# BG96.net
KiCad netlist of a schematic drawn in Altium Designer
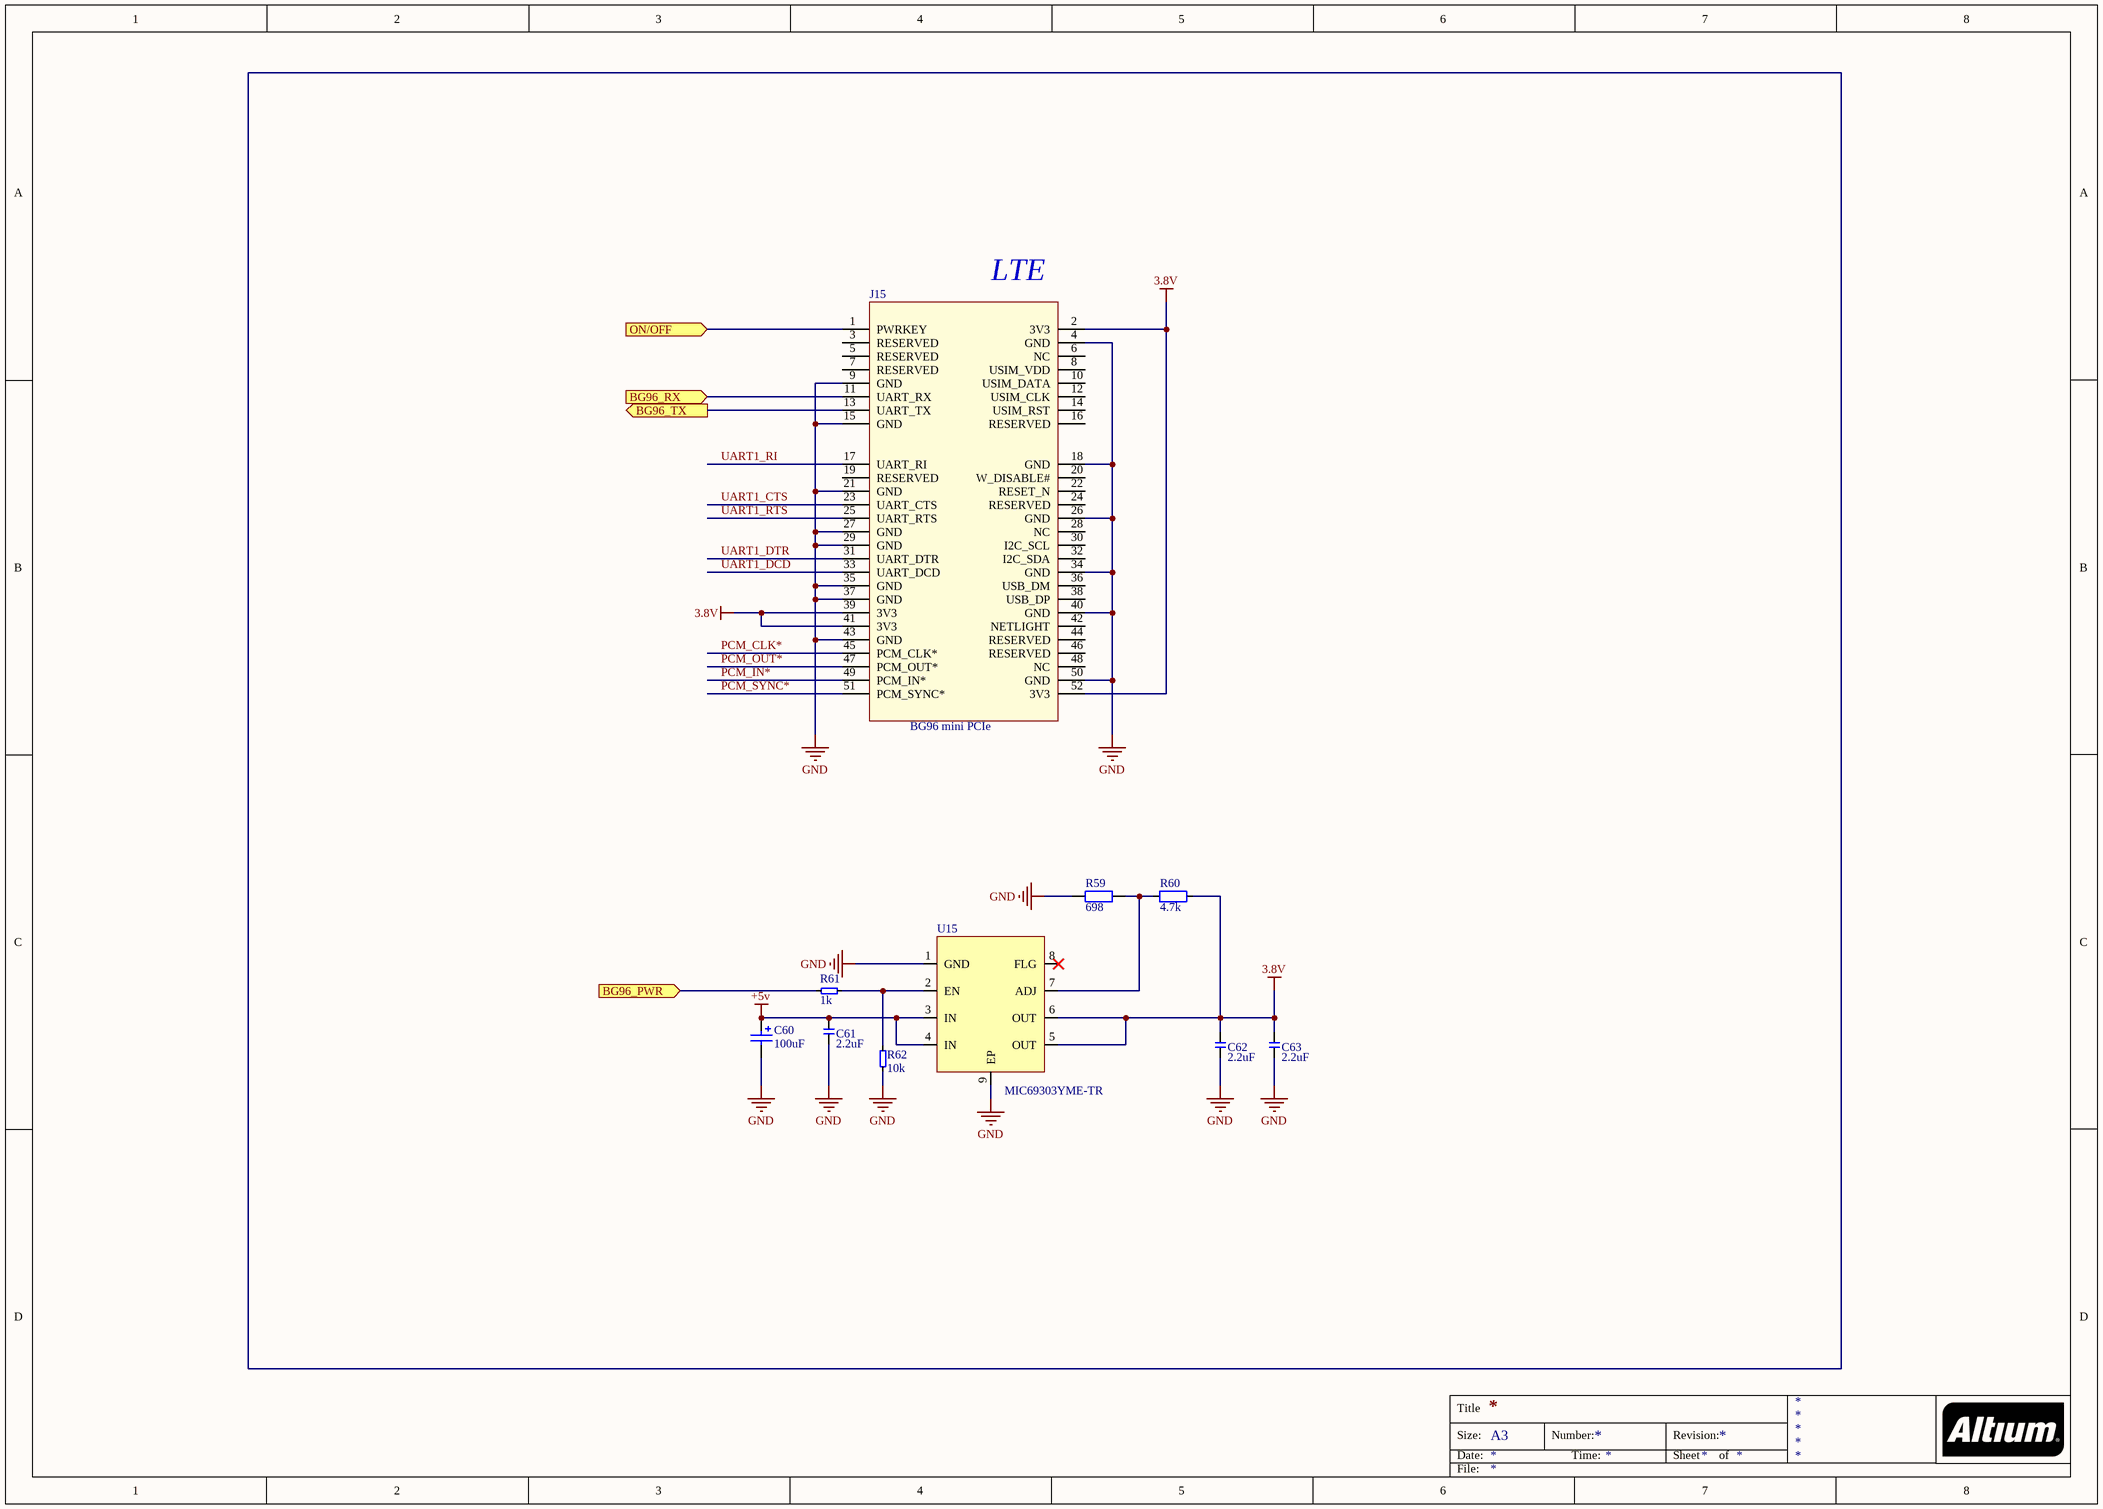
[diagram p0: BG96.SchDoc]

(export (version "E")
  (design (tool "Eeschema 10.0.6"))
  (components
    (comp (ref "C60")
      (value "100uF")
      (footprint "C_Tantalum_1206_(3.20mm x 1.60mm)")
      (description "CAP TANT 100UF 10% 6.3V 1206")
      (fields
        (field (name "MANUFACTURER") "Kyocera AVX")
        (field (name "MANUFACTURER PART NUMBER") "F930J107KAA")
      )
      (libsource (lib "Miscellaneous Devices") (part "Cap Pol2"))
    )
    (comp (ref "C61")
      (value "2.2uF")
      (footprint "C0603")
      (description "CAP CER 2.2UF 10V X7R 0603")
      (fields
        (field (name "MANUFACTURER") "Samsung")
        (field (name "MANUFACTURER PART NUMBER") "CL10B225KP8NNNC")
      )
      (libsource (lib "LED_LIB") (part "CAP_0603"))
    )
    (comp (ref "C62")
      (value "2.2uF")
      (footprint "C0603")
      (description "CAP CER 2.2UF 10V X7R 0603")
      (fields
        (field (name "MANUFACTURER") "Samsung")
        (field (name "MANUFACTURER PART NUMBER") "CL10B225KP8NNNC")
      )
      (libsource (lib "LED_LIB") (part "CAP_0603"))
    )
    (comp (ref "C63")
      (value "2.2uF")
      (footprint "C0603")
      (description "CAP CER 2.2UF 10V X7R 0603")
      (fields
        (field (name "MANUFACTURER") "Samsung")
        (field (name "MANUFACTURER PART NUMBER") "CL10B225KP8NNNC")
      )
      (libsource (lib "LED_LIB") (part "CAP_0603"))
    )
    (comp (ref "J15")
      (value "BG96 mini PCIe")
      (footprint "MiniPCIe_67910-5700")
      (description "LTE duaghter board")
      (fields
        (field (name "MANUFACTURER") "Texas Instruments")
        (field (name "MANUFACTURER PART NUMBER") "TPS54561DPRR")
      )
      (libsource (lib "4ADI_2DO") (part "BG96 mini PCIe"))
    )
    (comp (ref "R59")
      (value "698")
      (footprint "R0603")
      (description "RES SMD 698 OHM 1% 1/10W 0603")
      (fields
        (field (name "MANUFACTURER") "Yageo")
        (field (name "MANUFACTURER PART NUMBER") "RC0603FR-07698RL")
      )
      (libsource (lib "Miscellaneous Devices") (part "Res2"))
    )
    (comp (ref "R60")
      (value "4.7k")
      (footprint "R0603")
      (description "RES SMD 4.7K OHM 1% 1/10W 0603")
      (fields
        (field (name "MANUFACTURER") "Yageo Phycomp")
        (field (name "MANUFACTURER PART NUMBER") "RC0603FR-074K7L")
      )
      (libsource (lib "MY SCH LIB") (part "Res_0603"))
    )
    (comp (ref "R61")
      (value "1k")
      (footprint "R_0603")
      (description "RES SMD 1K OHM 1% 1/10W 0603")
      (fields
        (field (name "MANUFACTURER") "Yageo")
        (field (name "MANUFACTURER PART NUMBER") "RC0603FR-071KL")
      )
      (libsource (lib "LED_LIB") (part "R_0402"))
    )
    (comp (ref "R62")
      (value "10k")
      (footprint "R_0603")
      (description "RES SMD 10K OHM 1% 1/10W 0603")
      (fields
        (field (name "MANUFACTURER") "Yageo")
        (field (name "MANUFACTURER PART NUMBER") "RC0603FR-0710KL")
      )
      (libsource (lib "LED_LIB") (part "R_0402"))
    )
    (comp (ref "U15")
      (value "MIC69303YME-TR")
      (footprint "soic8 PowerPad")
      (description "IC REG LINEAR POS ADJ 3A 8SOIC")
      (fields (field (name "MANUFACTURER") "Microchip Technology"))
      (libsource (lib "4ADI_2DO") (part "MIC69303YME-TR"))
    )
  )
  (nets
    (net (code "1") (name "+5v") (class "Default")
      (node (ref "C60") (pin "1") (pinfunction "1_1") (pintype "passive"))
      (node (ref "C61") (pin "2") (pinfunction "2_2") (pintype "passive"))
      (node (ref "U15") (pin "3") (pinfunction "IN_3") (pintype "passive"))
      (node (ref "U15") (pin "4") (pinfunction "IN_4") (pintype "passive"))
    )
    (net (code "2") (name "/BG96_PWR") (class "Default")
      (node (ref "R61") (pin "1") (pinfunction "1_1") (pintype "passive"))
    )
    (net (code "3") (name "/BG96_RX") (class "Default")
      (node (ref "J15") (pin "11") (pinfunction "UART_RX_11") (pintype "passive"))
    )
    (net (code "4") (name "/BG96_TX") (class "Default")
      (node (ref "J15") (pin "13") (pinfunction "UART_TX_13") (pintype "passive"))
    )
    (net (code "5") (name "/ON{slash}OFF") (class "Default")
      (node (ref "J15") (pin "1") (pinfunction "PWRKEY_1") (pintype "passive"))
    )
    (net (code "6") (name "/PCM_CLK*") (class "Default")
      (node (ref "J15") (pin "45") (pinfunction "PCM_CLK*_45") (pintype "passive"))
    )
    (net (code "7") (name "/PCM_IN*") (class "Default")
      (node (ref "J15") (pin "49") (pinfunction "PCM_IN*_49") (pintype "passive"))
    )
    (net (code "8") (name "/PCM_OUT*") (class "Default")
      (node (ref "J15") (pin "47") (pinfunction "PCM_OUT*_47") (pintype "passive"))
    )
    (net (code "9") (name "/PCM_SYNC*") (class "Default")
      (node (ref "J15") (pin "51") (pinfunction "PCM_SYNC*_51") (pintype "passive"))
    )
    (net (code "10") (name "/UART1_CTS") (class "Default")
      (node (ref "J15") (pin "23") (pinfunction "UART_CTS_23") (pintype "passive"))
    )
    (net (code "11") (name "/UART1_DCD") (class "Default")
      (node (ref "J15") (pin "33") (pinfunction "UART_DCD_33") (pintype "passive"))
    )
    (net (code "12") (name "/UART1_DTR") (class "Default")
      (node (ref "J15") (pin "31") (pinfunction "UART_DTR_31") (pintype "passive"))
    )
    (net (code "13") (name "/UART1_RI") (class "Default")
      (node (ref "J15") (pin "17") (pinfunction "UART_RI_17") (pintype "passive"))
    )
    (net (code "14") (name "/UART1_RTS") (class "Default")
      (node (ref "J15") (pin "25") (pinfunction "UART_RTS_25") (pintype "passive"))
    )
    (net (code "15") (name "3.8V") (class "Default")
      (node (ref "C62") (pin "2") (pinfunction "2_2") (pintype "passive"))
      (node (ref "C63") (pin "2") (pinfunction "2_2") (pintype "passive"))
      (node (ref "J15") (pin "2") (pinfunction "3V3_2") (pintype "passive"))
      (node (ref "J15") (pin "39") (pinfunction "3V3_39") (pintype "passive"))
      (node (ref "J15") (pin "41") (pinfunction "3V3_41") (pintype "passive"))
      (node (ref "J15") (pin "52") (pinfunction "3V3_52") (pintype "passive"))
      (node (ref "R60") (pin "1") (pinfunction "1_1") (pintype "passive"))
      (node (ref "U15") (pin "5") (pinfunction "OUT_5") (pintype "passive"))
      (node (ref "U15") (pin "6") (pinfunction "OUT_6") (pintype "passive"))
    )
    (net (code "16") (name "GND") (class "Default")
      (node (ref "C60") (pin "2") (pinfunction "2_2") (pintype "passive"))
      (node (ref "C61") (pin "1") (pinfunction "1_1") (pintype "passive"))
      (node (ref "C62") (pin "1") (pinfunction "1_1") (pintype "passive"))
      (node (ref "C63") (pin "1") (pinfunction "1_1") (pintype "passive"))
      (node (ref "J15") (pin "15") (pinfunction "GND_15") (pintype "passive"))
      (node (ref "J15") (pin "18") (pinfunction "GND_18") (pintype "passive"))
      (node (ref "J15") (pin "21") (pinfunction "GND_21") (pintype "passive"))
      (node (ref "J15") (pin "26") (pinfunction "GND_26") (pintype "passive"))
      (node (ref "J15") (pin "27") (pinfunction "GND_27") (pintype "passive"))
      (node (ref "J15") (pin "29") (pinfunction "GND_29") (pintype "passive"))
      (node (ref "J15") (pin "34") (pinfunction "GND_34") (pintype "passive"))
      (node (ref "J15") (pin "35") (pinfunction "GND_35") (pintype "passive"))
      (node (ref "J15") (pin "37") (pinfunction "GND_37") (pintype "passive"))
      (node (ref "J15") (pin "4") (pinfunction "GND_4") (pintype "passive"))
      (node (ref "J15") (pin "40") (pinfunction "GND_40") (pintype "passive"))
      (node (ref "J15") (pin "43") (pinfunction "GND_43") (pintype "passive"))
      (node (ref "J15") (pin "50") (pinfunction "GND_50") (pintype "passive"))
      (node (ref "J15") (pin "9") (pinfunction "GND_9") (pintype "passive"))
      (node (ref "R59") (pin "2") (pinfunction "2_2") (pintype "passive"))
      (node (ref "R62") (pin "2") (pinfunction "2_2") (pintype "passive"))
      (node (ref "U15") (pin "1") (pinfunction "GND_1") (pintype "passive"))
      (node (ref "U15") (pin "9") (pinfunction "EP_9") (pintype "passive"))
    )
    (net (code "17") (name "Net-(U15-ADJ)") (class "Default")
      (node (ref "R59") (pin "1") (pinfunction "1_1") (pintype "passive"))
      (node (ref "R60") (pin "2") (pinfunction "2_2") (pintype "passive"))
      (node (ref "U15") (pin "7") (pinfunction "ADJ_7") (pintype "passive"))
    )
    (net (code "18") (name "Net-(U15-EN)") (class "Default")
      (node (ref "R61") (pin "2") (pinfunction "2_2") (pintype "passive"))
      (node (ref "R62") (pin "1") (pinfunction "1_1") (pintype "passive"))
      (node (ref "U15") (pin "2") (pinfunction "EN_2") (pintype "passive"))
    )
    (net (code "19") (name "unconnected-(J15-I2C_SCL-Pad30)") (class "Default")
      (node (ref "J15") (pin "30") (pinfunction "I2C_SCL_30") (pintype "passive"))
    )
    (net (code "20") (name "unconnected-(J15-I2C_SDA-Pad32)") (class "Default")
      (node (ref "J15") (pin "32") (pinfunction "I2C_SDA_32") (pintype "passive"))
    )
    (net (code "21") (name "unconnected-(J15-NC-Pad6)") (class "Default")
      (node (ref "J15") (pin "6") (pinfunction "NC_6") (pintype "passive"))
    )
    (net (code "22") (name "unconnected-(J15-NC-Pad28)") (class "Default")
      (node (ref "J15") (pin "28") (pinfunction "NC_28") (pintype "passive"))
    )
    (net (code "23") (name "unconnected-(J15-NC-Pad48)") (class "Default")
      (node (ref "J15") (pin "48") (pinfunction "NC_48") (pintype "passive"))
    )
    (net (code "24") (name "unconnected-(J15-NETLIGHT-Pad42)") (class "Default")
      (node (ref "J15") (pin "42") (pinfunction "NETLIGHT_42") (pintype "passive"))
    )
    (net (code "25") (name "unconnected-(J15-RESERVED-Pad3)") (class "Default")
      (node (ref "J15") (pin "3") (pinfunction "RESERVED_3") (pintype "passive"))
    )
    (net (code "26") (name "unconnected-(J15-RESERVED-Pad5)") (class "Default")
      (node (ref "J15") (pin "5") (pinfunction "RESERVED_5") (pintype "passive"))
    )
    (net (code "27") (name "unconnected-(J15-RESERVED-Pad7)") (class "Default")
      (node (ref "J15") (pin "7") (pinfunction "RESERVED_7") (pintype "passive"))
    )
    (net (code "28") (name "unconnected-(J15-RESERVED-Pad16)") (class "Default")
      (node (ref "J15") (pin "16") (pinfunction "RESERVED_16") (pintype "passive"))
    )
    (net (code "29") (name "unconnected-(J15-RESERVED-Pad19)") (class "Default")
      (node (ref "J15") (pin "19") (pinfunction "RESERVED_19") (pintype "passive"))
    )
    (net (code "30") (name "unconnected-(J15-RESERVED-Pad24)") (class "Default")
      (node (ref "J15") (pin "24") (pinfunction "RESERVED_24") (pintype "passive"))
    )
    (net (code "31") (name "unconnected-(J15-RESERVED-Pad44)") (class "Default")
      (node (ref "J15") (pin "44") (pinfunction "RESERVED_44") (pintype "passive"))
    )
    (net (code "32") (name "unconnected-(J15-RESERVED-Pad46)") (class "Default")
      (node (ref "J15") (pin "46") (pinfunction "RESERVED_46") (pintype "passive"))
    )
    (net (code "33") (name "unconnected-(J15-RESET_N-Pad22)") (class "Default")
      (node (ref "J15") (pin "22") (pinfunction "RESET_N_22") (pintype "passive"))
    )
    (net (code "34") (name "unconnected-(J15-USB_DM-Pad36)") (class "Default")
      (node (ref "J15") (pin "36") (pinfunction "USB_DM_36") (pintype "passive"))
    )
    (net (code "35") (name "unconnected-(J15-USB_DP-Pad38)") (class "Default")
      (node (ref "J15") (pin "38") (pinfunction "USB_DP_38") (pintype "passive"))
    )
    (net (code "36") (name "unconnected-(J15-USIM_CLK-Pad12)") (class "Default")
      (node (ref "J15") (pin "12") (pinfunction "USIM_CLK_12") (pintype "passive"))
    )
    (net (code "37") (name "unconnected-(J15-USIM_DATA-Pad10)") (class "Default")
      (node (ref "J15") (pin "10") (pinfunction "USIM_DATA_10") (pintype "passive"))
    )
    (net (code "38") (name "unconnected-(J15-USIM_RST-Pad14)") (class "Default")
      (node (ref "J15") (pin "14") (pinfunction "USIM_RST_14") (pintype "passive"))
    )
    (net (code "39") (name "unconnected-(J15-USIM_VDD-Pad8)") (class "Default")
      (node (ref "J15") (pin "8") (pinfunction "USIM_VDD_8") (pintype "passive"))
    )
    (net (code "40") (name "unconnected-(J15-W_DISABLE#-Pad20)") (class "Default")
      (node (ref "J15") (pin "20") (pinfunction "W_DISABLE#_20") (pintype "passive"))
    )
    (net (code "41") (name "unconnected-(U15-FLG-Pad8)") (class "Default")
      (node (ref "U15") (pin "8") (pinfunction "FLG_8") (pintype "passive+no_connect"))
    )
  )
)
